# PowerBoard.net
KiCad netlist of a schematic drawn in Altium Designer
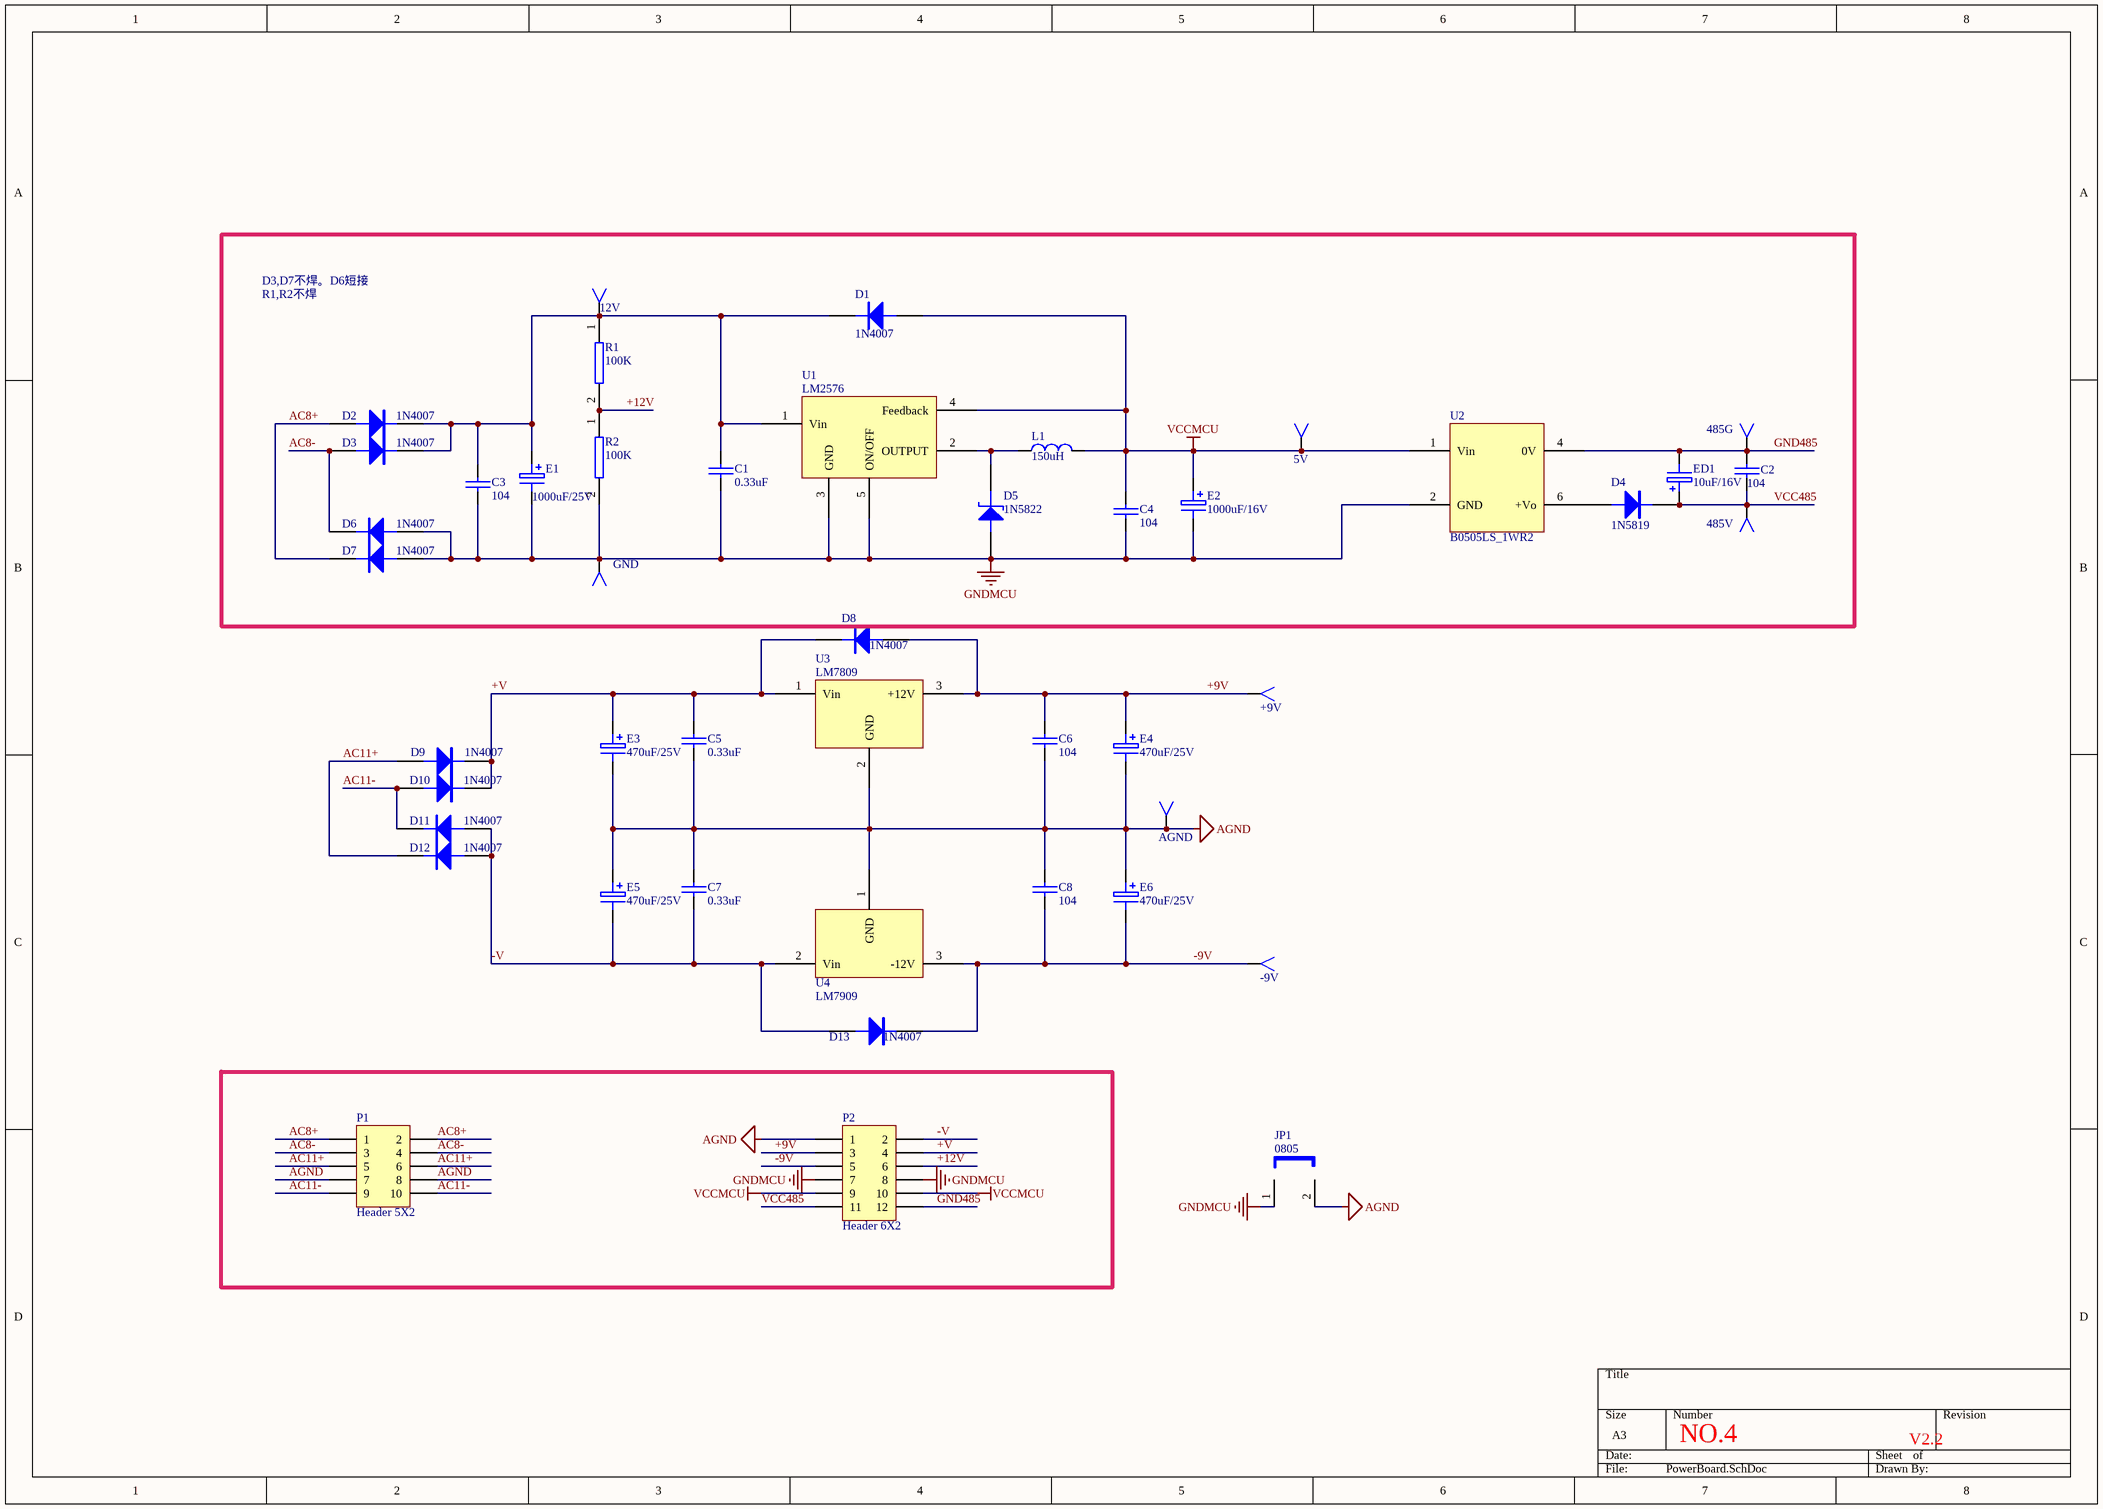
[diagram p0: PowerBoard.SchDoc]

(export (version "E")
  (design (tool "Eeschema 10.0.6"))
  (components
    (comp (ref "+9V")
      (value "TestPoint")
      (footprint "TestPoint_1.5")
      (libsource (lib "YGInfoSCHLib") (part "TestPoint"))
    )
    (comp (ref "-9V")
      (value "TestPoint")
      (footprint "TestPoint_1.5")
      (libsource (lib "YGInfoSCHLib") (part "TestPoint"))
    )
    (comp (ref "5V")
      (value "TestPoint")
      (footprint "TestPoint_1.5")
      (libsource (lib "YGInfoSCHLib") (part "TestPoint"))
    )
    (comp (ref "12V")
      (value "TestPoint")
      (footprint "TestPoint_1.5")
      (libsource (lib "YGInfoSCHLib") (part "TestPoint"))
    )
    (comp (ref "485G")
      (value "TestPoint")
      (footprint "TestPoint_1.5")
      (libsource (lib "YGInfoSCHLib") (part "TestPoint"))
    )
    (comp (ref "485V")
      (value "TestPoint")
      (footprint "TestPoint_1.5")
      (libsource (lib "YGInfoSCHLib") (part "TestPoint"))
    )
    (comp (ref "AGND")
      (value "TestPoint")
      (footprint "TestPoint_1.5")
      (libsource (lib "YGInfoSCHLib") (part "TestPoint"))
    )
    (comp (ref "C1") (value "0.33uF") (footprint "CAP200") (libsource (lib "*") (part "CAP")))
    (comp (ref "C2")
      (value "104")
      (footprint "0805/C2")
      (description "Capacitor")
      (libsource (lib "") (part "CAP_1"))
    )
    (comp (ref "C3")
      (value "104")
      (footprint "cap200")
      (description "Capacitor")
      (libsource (lib "") (part "CAP_1"))
    )
    (comp (ref "C4") (value "104") (footprint "cap200") (libsource (lib "*") (part "CAP")))
    (comp (ref "C5") (value "0.33uF") (footprint "cap200") (libsource (lib "YGInfoSCHLib") (part "CAP")))
    (comp (ref "C6") (value "104") (footprint "cap200") (libsource (lib "YGInfoSCHLib") (part "CAP")))
    (comp (ref "C7") (value "0.33uF") (footprint "cap200") (libsource (lib "YGInfoSCHLib") (part "CAP")))
    (comp (ref "C8") (value "104") (footprint "cap200") (libsource (lib "YGInfoSCHLib") (part "CAP")))
    (comp (ref "D1")
      (value "1N4007")
      (footprint "DIODE0.3")
      (description "Diode")
      (libsource (lib "*") (part "DIODE"))
    )
    (comp (ref "D2")
      (value "1N4007")
      (footprint "DIODE0.3")
      (description "Diode")
      (libsource (lib "YGInfoSCHLib") (part "DIODE"))
    )
    (comp (ref "D3")
      (value "1N4007")
      (footprint "DIODE0.3")
      (description "Diode")
      (libsource (lib "YGInfoSCHLib") (part "DIODE"))
    )
    (comp (ref "D4")
      (value "1N5819")
      (footprint "DIODE0.3")
      (description "Diode")
      (libsource (lib "YGInfoSCHLib") (part "DIODE"))
    )
    (comp (ref "D5")
      (value "1N5822")
      (footprint "SB540")
      (description "Zener Diode")
      (libsource (lib "*") (part "ZENER2"))
    )
    (comp (ref "D6")
      (value "1N4007")
      (footprint "DIODE0.3")
      (description "Diode")
      (libsource (lib "YGInfoSCHLib") (part "DIODE"))
    )
    (comp (ref "D7")
      (value "1N4007")
      (footprint "DIODE0.3")
      (description "Diode")
      (libsource (lib "YGInfoSCHLib") (part "DIODE"))
    )
    (comp (ref "D8")
      (value "1N4007")
      (footprint "DIODE0.3")
      (description "Diode")
      (libsource (lib "YGInfoSCHLib") (part "DIODE"))
    )
    (comp (ref "D9")
      (value "1N4007")
      (footprint "DIODE0.3")
      (description "Diode")
      (libsource (lib "YGInfoSCHLib") (part "DIODE"))
    )
    (comp (ref "D10")
      (value "1N4007")
      (footprint "DIODE0.3")
      (description "Diode")
      (libsource (lib "YGInfoSCHLib") (part "DIODE"))
    )
    (comp (ref "D11")
      (value "1N4007")
      (footprint "DIODE0.3")
      (description "Diode")
      (libsource (lib "YGInfoSCHLib") (part "DIODE"))
    )
    (comp (ref "D12")
      (value "1N4007")
      (footprint "DIODE0.3")
      (description "Diode")
      (libsource (lib "YGInfoSCHLib") (part "DIODE"))
    )
    (comp (ref "D13")
      (value "1N4007")
      (footprint "DIODE0.3")
      (description "Diode")
      (libsource (lib "YGInfoSCHLib") (part "DIODE"))
    )
    (comp (ref "E1")
      (value "1000uF/25V")
      (footprint "rb.2/.4")
      (libsource (lib "YGInfoSCHLib") (part "ELECTRO1"))
    )
    (comp (ref "E2") (value "1000uF/16V") (footprint "rb.2/.4") (libsource (lib "*") (part "ELECTRO1")))
    (comp (ref "E3")
      (value "470uF/25V")
      (footprint "C-220UF")
      (libsource (lib "YGInfoSCHLib") (part "ELECTRO1"))
    )
    (comp (ref "E4")
      (value "470uF/25V")
      (footprint "C-220UF")
      (libsource (lib "YGInfoSCHLib") (part "ELECTRO1"))
    )
    (comp (ref "E5")
      (value "470uF/25V")
      (footprint "C-220UF")
      (libsource (lib "YGInfoSCHLib") (part "ELECTRO1"))
    )
    (comp (ref "E6")
      (value "470uF/25V")
      (footprint "C-220UF")
      (libsource (lib "YGInfoSCHLib") (part "ELECTRO1"))
    )
    (comp (ref "ED1")
      (value "10uF/16V")
      (footprint "3528")
      (libsource (lib "YGInfoSCHLib") (part "ELECTRO1"))
    )
    (comp (ref "GND")
      (value "TestPoint")
      (footprint "TestPoint_1.5")
      (libsource (lib "YGInfoSCHLib") (part "TestPoint"))
    )
    (comp (ref "JP1")
      (value "0805")
      (footprint "0805/R")
      (description "Jumper")
      (libsource (lib "YGInfoSCHLib") (part "JUMPER"))
    )
    (comp (ref "L1") (value "150uH") (footprint "L-100UH") (libsource (lib "*") (part "L")))
    (comp (ref "P1")
      (value "Header 5X2")
      (footprint "HDR2X5")
      (description "Header, 5-Pin, Dual row")
      (fields (field (name "PUBLISHER") "Altium Limited"))
      (libsource (lib "YGInfoSCHLib") (part "Header 5X2"))
    )
    (comp (ref "P2")
      (value "Header 6X2")
      (footprint "HDR2X6")
      (description "Header, 6-Pin, Dual row")
      (fields (field (name "PUBLISHER") "Altium Limited"))
      (libsource (lib "YGInfoSCHLib") (part "Header 6X2"))
    )
    (comp (ref "R1") (value "100K") (footprint "0805/R") (libsource (lib "YGInfoSCHLib") (part "RES2")))
    (comp (ref "R2") (value "100K") (footprint "0805/R") (libsource (lib "YGInfoSCHLib") (part "RES2")))
    (comp (ref "U1") (value "LM2576") (footprint "TO-263 - 5") (libsource (lib "*") (part "LM2576")))
    (comp (ref "U2")
      (value "B0505LS_1WR2")
      (footprint "B0505LS-1WR2")
      (libsource (lib "YGInfoSCHLib") (part "B0505LS_1WR2"))
    )
    (comp (ref "U3") (value "LM7809") (footprint "78XX") (libsource (lib "YGInfoSCHLib") (part "MC7812T")))
    (comp (ref "U4") (value "LM7909") (footprint "78XX") (libsource (lib "YGInfoSCHLib") (part "MC7912T")))
  )
  (nets
    (net (code "1") (name "/+9V") (class "Default")
      (node (ref "+9V") (pin "1") (pinfunction "1_1") (pintype "power_in"))
      (node (ref "C6") (pin "1") (pintype "passive"))
      (node (ref "D8") (pin "1") (pinfunction "A_1") (pintype "passive"))
      (node (ref "E4") (pin "1") (pintype "passive"))
      (node (ref "P2") (pin "3") (pinfunction "3_3") (pintype "passive"))
      (node (ref "U3") (pin "3") (pinfunction "+12V_3") (pintype "passive"))
    )
    (net (code "2") (name "/+12V") (class "Default")
      (node (ref "P2") (pin "6") (pinfunction "6_6") (pintype "passive"))
      (node (ref "R1") (pin "2") (pinfunction "2_2") (pintype "passive"))
      (node (ref "R2") (pin "1") (pinfunction "1_1") (pintype "passive"))
    )
    (net (code "3") (name "/+V") (class "Default")
      (node (ref "C5") (pin "1") (pintype "passive"))
      (node (ref "D10") (pin "2") (pinfunction "K_2") (pintype "passive"))
      (node (ref "D8") (pin "2") (pinfunction "K_2") (pintype "passive"))
      (node (ref "D9") (pin "2") (pinfunction "K_2") (pintype "passive"))
      (node (ref "E3") (pin "1") (pintype "passive"))
      (node (ref "P2") (pin "4") (pinfunction "4_4") (pintype "passive"))
      (node (ref "U3") (pin "1") (pinfunction "Vin_1") (pintype "passive"))
    )
    (net (code "4") (name "/-9V") (class "Default")
      (node (ref "-9V") (pin "1") (pinfunction "1_1") (pintype "power_in"))
      (node (ref "C8") (pin "2") (pintype "passive"))
      (node (ref "D13") (pin "2") (pinfunction "K_2") (pintype "passive"))
      (node (ref "E6") (pin "2") (pintype "passive"))
      (node (ref "P2") (pin "5") (pinfunction "5_5") (pintype "passive"))
      (node (ref "U4") (pin "3") (pinfunction "-12V_3") (pintype "passive"))
    )
    (net (code "5") (name "/-V") (class "Default")
      (node (ref "C7") (pin "2") (pintype "passive"))
      (node (ref "D11") (pin "1") (pinfunction "A_1") (pintype "passive"))
      (node (ref "D12") (pin "1") (pinfunction "A_1") (pintype "passive"))
      (node (ref "D13") (pin "1") (pinfunction "A_1") (pintype "passive"))
      (node (ref "E5") (pin "2") (pintype "passive"))
      (node (ref "P2") (pin "2") (pinfunction "2_2") (pintype "passive"))
      (node (ref "U4") (pin "2") (pinfunction "Vin_2") (pintype "passive"))
    )
    (net (code "6") (name "/AC8+") (class "Default")
      (node (ref "D2") (pin "1") (pinfunction "A_1") (pintype "passive"))
      (node (ref "D7") (pin "2") (pinfunction "K_2") (pintype "passive"))
      (node (ref "P1") (pin "1") (pinfunction "1_1") (pintype "passive"))
      (node (ref "P1") (pin "2") (pinfunction "2_2") (pintype "passive"))
    )
    (net (code "7") (name "/AC8-") (class "Default")
      (node (ref "D3") (pin "1") (pinfunction "A_1") (pintype "passive"))
      (node (ref "D6") (pin "2") (pinfunction "K_2") (pintype "passive"))
      (node (ref "P1") (pin "3") (pinfunction "3_3") (pintype "passive"))
      (node (ref "P1") (pin "4") (pinfunction "4_4") (pintype "passive"))
    )
    (net (code "8") (name "/AC11+") (class "Default")
      (node (ref "D12") (pin "2") (pinfunction "K_2") (pintype "passive"))
      (node (ref "D9") (pin "1") (pinfunction "A_1") (pintype "passive"))
      (node (ref "P1") (pin "5") (pinfunction "5_5") (pintype "passive"))
      (node (ref "P1") (pin "6") (pinfunction "6_6") (pintype "passive"))
    )
    (net (code "9") (name "/AC11-") (class "Default")
      (node (ref "D10") (pin "1") (pinfunction "A_1") (pintype "passive"))
      (node (ref "D11") (pin "2") (pinfunction "K_2") (pintype "passive"))
      (node (ref "P1") (pin "10") (pinfunction "10_10") (pintype "passive"))
      (node (ref "P1") (pin "9") (pinfunction "9_9") (pintype "passive"))
    )
    (net (code "10") (name "/GND485") (class "Default")
      (node (ref "485G") (pin "1") (pinfunction "1_1") (pintype "power_in"))
      (node (ref "C2") (pin "1") (pinfunction "1_1") (pintype "passive"))
      (node (ref "ED1") (pin "2") (pintype "passive"))
      (node (ref "P2") (pin "12") (pinfunction "12_12") (pintype "passive"))
      (node (ref "U2") (pin "4") (pinfunction "0V_4") (pintype "passive"))
    )
    (net (code "11") (name "/VCC485") (class "Default")
      (node (ref "485V") (pin "1") (pinfunction "1_1") (pintype "power_in"))
      (node (ref "C2") (pin "2") (pinfunction "2_2") (pintype "passive"))
      (node (ref "D4") (pin "2") (pinfunction "K_2") (pintype "passive"))
      (node (ref "ED1") (pin "1") (pintype "passive"))
      (node (ref "P2") (pin "11") (pinfunction "11_11") (pintype "passive"))
    )
    (net (code "12") (name "AGND") (class "Default")
      (node (ref "AGND") (pin "1") (pinfunction "1_1") (pintype "power_in"))
      (node (ref "C5") (pin "2") (pintype "passive"))
      (node (ref "C6") (pin "2") (pintype "passive"))
      (node (ref "C7") (pin "1") (pintype "passive"))
      (node (ref "C8") (pin "1") (pintype "passive"))
      (node (ref "E3") (pin "2") (pintype "passive"))
      (node (ref "E4") (pin "2") (pintype "passive"))
      (node (ref "E5") (pin "1") (pintype "passive"))
      (node (ref "E6") (pin "1") (pintype "passive"))
      (node (ref "JP1") (pin "2") (pinfunction "2_2") (pintype "passive"))
      (node (ref "P1") (pin "7") (pinfunction "7_7") (pintype "passive"))
      (node (ref "P1") (pin "8") (pinfunction "8_8") (pintype "passive"))
      (node (ref "P2") (pin "1") (pinfunction "1_1") (pintype "passive"))
      (node (ref "U3") (pin "2") (pinfunction "GND_2") (pintype "passive"))
      (node (ref "U4") (pin "1") (pinfunction "GND_1") (pintype "passive"))
    )
    (net (code "13") (name "GNDMCU") (class "Default")
      (node (ref "C1") (pin "2") (pintype "passive"))
      (node (ref "C3") (pin "2") (pinfunction "2_2") (pintype "passive"))
      (node (ref "C4") (pin "2") (pintype "passive"))
      (node (ref "D5") (pin "1") (pinfunction "A_1") (pintype "passive"))
      (node (ref "D6") (pin "1") (pinfunction "A_1") (pintype "passive"))
      (node (ref "D7") (pin "1") (pinfunction "A_1") (pintype "passive"))
      (node (ref "E1") (pin "2") (pintype "passive"))
      (node (ref "E2") (pin "2") (pintype "passive"))
      (node (ref "GND") (pin "1") (pinfunction "1_1") (pintype "power_in"))
      (node (ref "JP1") (pin "1") (pinfunction "1_1") (pintype "passive"))
      (node (ref "P2") (pin "7") (pinfunction "7_7") (pintype "passive"))
      (node (ref "P2") (pin "8") (pinfunction "8_8") (pintype "passive"))
      (node (ref "R2") (pin "2") (pinfunction "2_2") (pintype "passive"))
      (node (ref "U1") (pin "3") (pinfunction "GND_3") (pintype "passive"))
      (node (ref "U1") (pin "5") (pinfunction "ON/OFF_5") (pintype "passive"))
      (node (ref "U2") (pin "2") (pinfunction "GND_2") (pintype "passive"))
    )
    (net (code "14") (name "Net-(D1-K)") (class "Default")
      (node (ref "12V") (pin "1") (pinfunction "1_1") (pintype "power_in"))
      (node (ref "C1") (pin "1") (pintype "passive"))
      (node (ref "C3") (pin "1") (pinfunction "1_1") (pintype "passive"))
      (node (ref "D1") (pin "2") (pinfunction "K_2") (pintype "passive"))
      (node (ref "D2") (pin "2") (pinfunction "K_2") (pintype "passive"))
      (node (ref "D3") (pin "2") (pinfunction "K_2") (pintype "passive"))
      (node (ref "E1") (pin "1") (pintype "passive"))
      (node (ref "R1") (pin "1") (pinfunction "1_1") (pintype "passive"))
      (node (ref "U1") (pin "1") (pinfunction "Vin_1") (pintype "passive"))
    )
    (net (code "15") (name "Net-(D4-A)") (class "Default")
      (node (ref "D4") (pin "1") (pinfunction "A_1") (pintype "passive"))
      (node (ref "U2") (pin "6") (pinfunction "+Vo_6") (pintype "passive"))
    )
    (net (code "16") (name "Net-(D5-K)") (class "Default")
      (node (ref "D5") (pin "2") (pinfunction "K_2") (pintype "passive"))
      (node (ref "L1") (pin "1") (pinfunction "1_1") (pintype "bidirectional"))
      (node (ref "U1") (pin "2") (pinfunction "OUTPUT_2") (pintype "passive"))
    )
    (net (code "17") (name "VCCMCU") (class "Default")
      (node (ref "5V") (pin "1") (pinfunction "1_1") (pintype "power_in"))
      (node (ref "C4") (pin "1") (pintype "passive"))
      (node (ref "D1") (pin "1") (pinfunction "A_1") (pintype "passive"))
      (node (ref "E2") (pin "1") (pintype "passive"))
      (node (ref "L1") (pin "2") (pinfunction "2_2") (pintype "passive"))
      (node (ref "P2") (pin "10") (pinfunction "10_10") (pintype "passive"))
      (node (ref "P2") (pin "9") (pinfunction "9_9") (pintype "passive"))
      (node (ref "U1") (pin "4") (pinfunction "Feedback_4") (pintype "passive"))
      (node (ref "U2") (pin "1") (pinfunction "Vin_1") (pintype "passive"))
    )
  )
)
